# UHF_RFID_READER_IC.net
KiCad netlist of a schematic drawn in Altium Designer
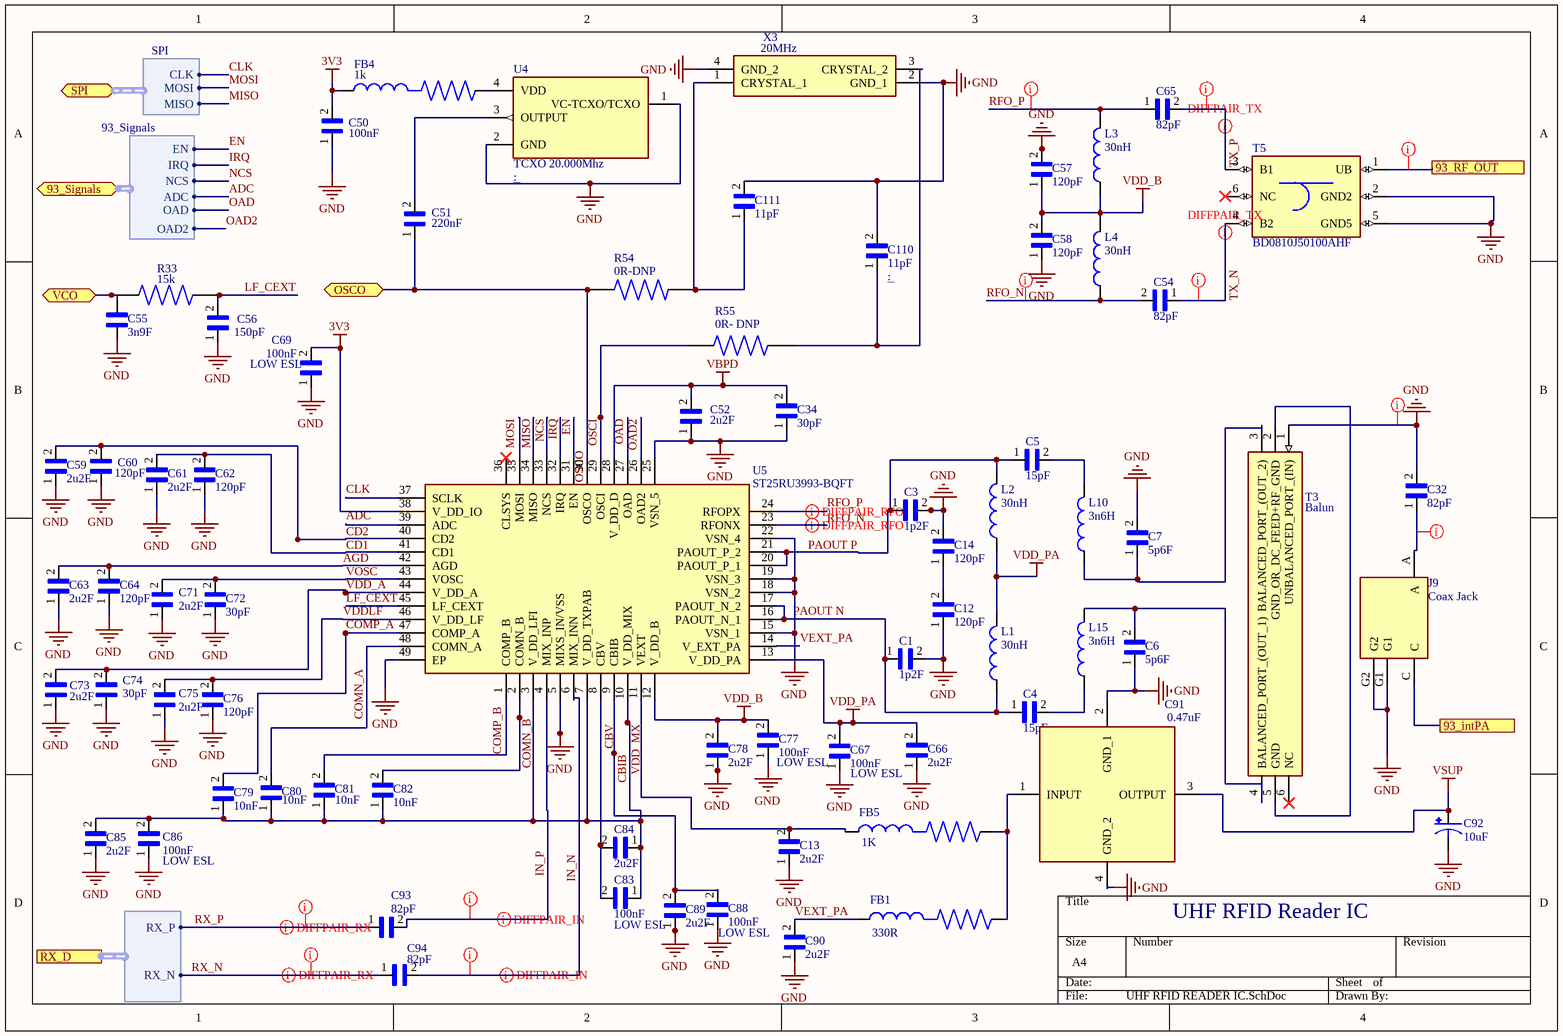
[diagram p0: UHF RFID READER IC.SchDoc]

(export (version "E")
  (design (tool "Eeschema 10.0.6"))
  (components
    (comp (ref "C1")
      (value "1p2F")
      (footprint "CAPC1005X55N")
      (description "SMD Capacitor C0G_EIA_ with Capacitance: 1.2pF Tol. 0.05pF. Rated Voltage: 50Vdc")
      (fields (field (name "MP") "GRM1555C1H1R2WA01D") (field (name "MF") "Murata Electronics"))
      (libsource (lib "GRM1555C1H1R2WA01D") (part "GRM1555C1H1R2WA01D"))
    )
    (comp (ref "C3")
      (value "1p2F")
      (footprint "CAPC1005X55N")
      (description "SMD Capacitor C0G_EIA_ with Capacitance: 1.2pF Tol. 0.05pF. Rated Voltage: 50Vdc")
      (fields (field (name "MP") "GRM1555C1H1R2WA01D") (field (name "MF") "Murata Electronics"))
      (libsource (lib "GRM1555C1H1R2WA01D") (part "GRM1555C1H1R2WA01D"))
    )
    (comp (ref "C4")
      (value "15pF")
      (footprint "CAPC1005X55N")
      (description "0402 15 pF 50 V Â±2% Tolerance C0G SMT Multilayer Ceramic Capacitor")
      (fields (field (name "MP") "GRM1555C1H150GA01D"))
      (libsource (lib "GRM1555C1H150GA01D") (part "GRM1555C1H150GA01D"))
    )
    (comp (ref "C5")
      (value "15pF")
      (footprint "CAPC1005X55N")
      (description "0402 15 pF 50 V Â±2% Tolerance C0G SMT Multilayer Ceramic Capacitor")
      (fields (field (name "MP") "GRM1555C1H150GA01D"))
      (libsource (lib "GRM1555C1H150GA01D") (part "GRM1555C1H150GA01D"))
    )
    (comp (ref "C6")
      (value "5p6F")
      (footprint "CAPC1005X55N")
      (description "SMD Capacitor C0G(EIA) with Capacitance: 5.6pF Tol. 0.25pF. Rated Voltage: 50Vdc")
      (fields (field (name "MF") "Murata") (field (name "MP") "GJM1555C1H5R6CB01D"))
      (libsource (lib "GJM1555C1H5R6CB01D") (part "GJM1555C1H5R6CB01D"))
    )
    (comp (ref "C7")
      (value "5p6F")
      (footprint "CAPC1005X55N")
      (description "SMD Capacitor C0G(EIA) with Capacitance: 5.6pF Tol. 0.25pF. Rated Voltage: 50Vdc")
      (fields (field (name "MF") "Murata") (field (name "MP") "GJM1555C1H5R6CB01D"))
      (libsource (lib "GJM1555C1H5R6CB01D") (part "GJM1555C1H5R6CB01D"))
    )
    (comp (ref "C12")
      (value "120pF")
      (footprint "CAPC0603X33N")
      (description "0201 120 pF 50 V Â±5% Tolerance C0G SMT Multilayer Ceramic Capacitor")
      (fields (field (name "MF") "Murata Electronics") (field (name "MP") "GRM0335C1H121JA01D"))
      (libsource (lib "") (part "GRM0335C1H121JA01D_1"))
    )
    (comp (ref "C13")
      (value "2u2F")
      (footprint "CAPC0603X35N")
      (description "SMD Capacitor X5R(EIA) with Capacitance: 2.2uF Tol. 20%. Rated Voltage: 6.3Vdc")
      (fields (field (name "MP") "GRM033R60J225ME15D"))
      (libsource (lib "GRM033R60J225ME15D") (part "GRM033R60J225ME15D"))
    )
    (comp (ref "C14")
      (value "120pF")
      (footprint "CAPC0603X33N")
      (description "0201 120 pF 50 V Â±5% Tolerance C0G SMT Multilayer Ceramic Capacitor")
      (fields (field (name "MF") "Murata Electronics") (field (name "MP") "GRM0335C1H121JA01D"))
      (libsource (lib "") (part "GRM0335C1H121JA01D_1"))
    )
    (comp (ref "C32")
      (value "82pF")
      (footprint "CAPC1005X55N")
      (description "CAP CER 82PF 50V C0G/NP0 0402")
      (fields (field (name "MP") "GRM1555C1H820GA01J"))
      (libsource (lib "GRM1555C1H820GA01J") (part "GRM1555C1H820GA01J"))
    )
    (comp (ref "C34")
      (value "30pF")
      (footprint "CAPC0603X33N")
      (description "SMD Capacitor C0G(EIA) with Capacitance: 30pF Tol. 2%. Rated Voltage: 50Vdc")
      (fields (field (name "MP") "GRM0335C1H300GA01D"))
      (libsource (lib "GRM0335C1H300GA01D") (part "GRM0335C1H300GA01D"))
    )
    (comp (ref "C50")
      (value "100nF")
      (footprint "CAPC1005X55N")
      (description "SMD Capacitor X7R_EIA_ with Capacitance: 0.10uF Tol. 10%. Rated Voltage: 16Vdc")
      (fields (field (name "MF") "Murata") (field (name "MP") "GRM155R71C104KA88D"))
      (libsource (lib "GRM155R71C104KA88D") (part "GRM155R71C104KA88D"))
    )
    (comp (ref "C51")
      (value "220nF")
      (footprint "CAPC1005X55N")
      (description "CAP CER 0.22UF 35V X5R 0402")
      (fields (field (name "MP") "GRM155R6YA224KE01D"))
      (libsource (lib "GRM155R6YA224KE01D") (part "GRM155R6YA224KE01D"))
    )
    (comp (ref "C52")
      (value "2u2F")
      (footprint "CAPC0603X35N")
      (description "SMD Capacitor X5R(EIA) with Capacitance: 2.2uF Tol. 20%. Rated Voltage: 6.3Vdc")
      (fields (field (name "MP") "GRM033R60J225ME15D"))
      (libsource (lib "GRM033R60J225ME15D") (part "GRM033R60J225ME15D"))
    )
    (comp (ref "C54")
      (value "82pF")
      (footprint "CAPC1005X55N")
      (description "CAP CER 82PF 50V C0G/NP0 0402")
      (fields (field (name "MP") "GRM1555C1H820GA01J"))
      (libsource (lib "") (part "GRM1555C1H820GA01J_3"))
    )
    (comp (ref "C55")
      (value "3n9F")
      (footprint "CAPC1005X55N")
      (description "0402 10 V 3900 pF ±5% Tolerance U2J Monolithic Ceramic Chip Capacitor")
      (fields (field (name "MF") "Murata") (field (name "MP") "GRM1557U1A392JA01D"))
      (libsource (lib "GRM1557U1A392JA01D") (part "GRM1557U1A392JA01D"))
    )
    (comp (ref "C56")
      (value "150pF")
      (footprint "CAPC1005X55N")
      (description "Cap Ceramic 150pF 50V C0G 1% SMD 0402 125Â°C Paper T/R")
      (fields (field (name "MP") "GRM1555C1H151FA01D"))
      (libsource (lib "GRM1555C1H151FA01D") (part "GRM1555C1H151FA01D"))
    )
    (comp (ref "C57")
      (value "120pF")
      (footprint "CAPC0603X33N")
      (description "0201 120 pF 50 V Â±5% Tolerance C0G SMT Multilayer Ceramic Capacitor")
      (fields (field (name "MF") "Murata Electronics") (field (name "MP") "GRM0335C1H121JA01D"))
      (libsource (lib "") (part "GRM0335C1H121JA01D_2"))
    )
    (comp (ref "C58")
      (value "120pF")
      (footprint "CAPC0603X33N")
      (description "0201 120 pF 50 V Â±5% Tolerance C0G SMT Multilayer Ceramic Capacitor")
      (fields (field (name "MF") "Murata Electronics") (field (name "MP") "GRM0335C1H121JA01D"))
      (libsource (lib "") (part "GRM0335C1H121JA01D_2"))
    )
    (comp (ref "C59")
      (value "2u2F")
      (footprint "CAPC0603X35N")
      (description "SMD Capacitor X5R(EIA) with Capacitance: 2.2uF Tol. 20%. Rated Voltage: 6.3Vdc")
      (fields (field (name "MP") "GRM033R60J225ME15D"))
      (libsource (lib "GRM033R60J225ME15D") (part "GRM033R60J225ME15D"))
    )
    (comp (ref "C60")
      (value "120pF")
      (footprint "CAPC0603X33N")
      (description "0201 120 pF 50 V Â±5% Tolerance C0G SMT Multilayer Ceramic Capacitor")
      (fields (field (name "MF") "Murata Electronics") (field (name "MP") "GRM0335C1H121JA01D"))
      (libsource (lib "GRM0335C1H121JA01D") (part "GRM0335C1H121JA01D"))
    )
    (comp (ref "C61")
      (value "2u2F")
      (footprint "CAPC0603X35N")
      (description "SMD Capacitor X5R(EIA) with Capacitance: 2.2uF Tol. 20%. Rated Voltage: 6.3Vdc")
      (fields (field (name "MP") "GRM033R60J225ME15D"))
      (libsource (lib "GRM033R60J225ME15D") (part "GRM033R60J225ME15D"))
    )
    (comp (ref "C62")
      (value "120pF")
      (footprint "CAPC0603X33N")
      (description "0201 120 pF 50 V Â±5% Tolerance C0G SMT Multilayer Ceramic Capacitor")
      (fields (field (name "MF") "Murata Electronics") (field (name "MP") "GRM0335C1H121JA01D"))
      (libsource (lib "GRM0335C1H121JA01D") (part "GRM0335C1H121JA01D"))
    )
    (comp (ref "C63")
      (value "2u2F")
      (footprint "CAPC0603X35N")
      (description "SMD Capacitor X5R(EIA) with Capacitance: 2.2uF Tol. 20%. Rated Voltage: 6.3Vdc")
      (fields (field (name "MP") "GRM033R60J225ME15D"))
      (libsource (lib "GRM033R60J225ME15D") (part "GRM033R60J225ME15D"))
    )
    (comp (ref "C64")
      (value "120pF")
      (footprint "CAPC0603X33N")
      (description "0201 120 pF 50 V Â±5% Tolerance C0G SMT Multilayer Ceramic Capacitor")
      (fields (field (name "MF") "Murata Electronics") (field (name "MP") "GRM0335C1H121JA01D"))
      (libsource (lib "GRM0335C1H121JA01D") (part "GRM0335C1H121JA01D"))
    )
    (comp (ref "C65")
      (value "82pF")
      (footprint "CAPC1005X55N")
      (description "CAP CER 82PF 50V C0G/NP0 0402")
      (fields (field (name "MP") "GRM1555C1H820GA01J"))
      (libsource (lib "") (part "GRM1555C1H820GA01J_2"))
    )
    (comp (ref "C66")
      (value "2u2F")
      (footprint "CAPC0603X35N")
      (description "SMD Capacitor X5R(EIA) with Capacitance: 2.2uF Tol. 20%. Rated Voltage: 6.3Vdc")
      (fields (field (name "MP") "GRM033R60J225ME15D"))
      (libsource (lib "GRM033R60J225ME15D") (part "GRM033R60J225ME15D"))
    )
    (comp (ref "C67")
      (value "100nF")
      (footprint "CAPC0510X35N")
      (description "SMD Capacitor X6S(EIA) with Capacitance: 0.10uF Tol. 20%. Rated Voltage: 6.3Vdc")
      (fields (field (name "MF") "Murata") (field (name "MP") "LLL153C80J104ME01E"))
      (libsource (lib "LLL153C80J104ME01E") (part "LLL153C80J104ME01E"))
    )
    (comp (ref "C69")
      (value "100nF")
      (footprint "CAPC0510X35N")
      (description "SMD Capacitor X6S(EIA) with Capacitance: 0.10uF Tol. 20%. Rated Voltage: 6.3Vdc")
      (fields (field (name "MF") "Murata") (field (name "MP") "LLL153C80J104ME01E"))
      (libsource (lib "LLL153C80J104ME01E") (part "LLL153C80J104ME01E"))
    )
    (comp (ref "C71")
      (value "2u2F")
      (footprint "CAPC0603X35N")
      (description "SMD Capacitor X5R(EIA) with Capacitance: 2.2uF Tol. 20%. Rated Voltage: 6.3Vdc")
      (fields (field (name "MP") "GRM033R60J225ME15D"))
      (libsource (lib "GRM033R60J225ME15D") (part "GRM033R60J225ME15D"))
    )
    (comp (ref "C72")
      (value "30pF")
      (footprint "CAPC0603X33N")
      (description "SMD Capacitor C0G(EIA) with Capacitance: 30pF Tol. 2%. Rated Voltage: 50Vdc")
      (fields (field (name "MP") "GRM0335C1H300GA01D"))
      (libsource (lib "GRM0335C1H300GA01D") (part "GRM0335C1H300GA01D"))
    )
    (comp (ref "C73")
      (value "2u2F")
      (footprint "CAPC0603X35N")
      (description "SMD Capacitor X5R(EIA) with Capacitance: 2.2uF Tol. 20%. Rated Voltage: 6.3Vdc")
      (fields (field (name "MP") "GRM033R60J225ME15D"))
      (libsource (lib "GRM033R60J225ME15D") (part "GRM033R60J225ME15D"))
    )
    (comp (ref "C74")
      (value "30pF")
      (footprint "CAPC0603X33N")
      (description "SMD Capacitor C0G(EIA) with Capacitance: 30pF Tol. 2%. Rated Voltage: 50Vdc")
      (fields (field (name "MP") "GRM0335C1H300GA01D"))
      (libsource (lib "GRM0335C1H300GA01D") (part "GRM0335C1H300GA01D"))
    )
    (comp (ref "C75")
      (value "2u2F")
      (footprint "CAPC0603X35N")
      (description "SMD Capacitor X5R(EIA) with Capacitance: 2.2uF Tol. 20%. Rated Voltage: 6.3Vdc")
      (fields (field (name "MP") "GRM033R60J225ME15D"))
      (libsource (lib "GRM033R60J225ME15D") (part "GRM033R60J225ME15D"))
    )
    (comp (ref "C76")
      (value "120pF")
      (footprint "CAPC0603X33N")
      (description "0201 120 pF 50 V Â±5% Tolerance C0G SMT Multilayer Ceramic Capacitor")
      (fields (field (name "MF") "Murata Electronics") (field (name "MP") "GRM0335C1H121JA01D"))
      (libsource (lib "GRM0335C1H121JA01D") (part "GRM0335C1H121JA01D"))
    )
    (comp (ref "C77")
      (value "100nF")
      (footprint "CAPC0510X35N")
      (description "SMD Capacitor X6S(EIA) with Capacitance: 0.10uF Tol. 20%. Rated Voltage: 6.3Vdc")
      (fields (field (name "MF") "Murata") (field (name "MP") "LLL153C80J104ME01E"))
      (libsource (lib "LLL153C80J104ME01E") (part "LLL153C80J104ME01E"))
    )
    (comp (ref "C78")
      (value "2u2F")
      (footprint "CAPC0603X35N")
      (description "SMD Capacitor X5R(EIA) with Capacitance: 2.2uF Tol. 20%. Rated Voltage: 6.3Vdc")
      (fields (field (name "MP") "GRM033R60J225ME15D"))
      (libsource (lib "GRM033R60J225ME15D") (part "GRM033R60J225ME15D"))
    )
    (comp (ref "C79")
      (value "10nF")
      (footprint "CAPC0603X33N")
      (description "SMD Capacitor X7R(EIA) with Capacitance: 10000pF Tol. 10%. Rated Voltage: 10Vdc")
      (fields (field (name "MP") "GRM033R71A103KA01D") (field (name "MF") "Murata"))
      (libsource (lib "GRM033R71A103KA01D") (part "GRM033R71A103KA01D"))
    )
    (comp (ref "C80")
      (value "10nF")
      (footprint "CAPC0603X33N")
      (description "SMD Capacitor X7R(EIA) with Capacitance: 10000pF Tol. 10%. Rated Voltage: 10Vdc")
      (fields (field (name "MP") "GRM033R71A103KA01D") (field (name "MF") "Murata"))
      (libsource (lib "GRM033R71A103KA01D") (part "GRM033R71A103KA01D"))
    )
    (comp (ref "C81")
      (value "10nF")
      (footprint "CAPC0603X33N")
      (description "SMD Capacitor X7R(EIA) with Capacitance: 10000pF Tol. 10%. Rated Voltage: 10Vdc")
      (fields (field (name "MP") "GRM033R71A103KA01D") (field (name "MF") "Murata"))
      (libsource (lib "GRM033R71A103KA01D") (part "GRM033R71A103KA01D"))
    )
    (comp (ref "C82")
      (value "10nF")
      (footprint "CAPC0603X33N")
      (description "SMD Capacitor X7R(EIA) with Capacitance: 10000pF Tol. 10%. Rated Voltage: 10Vdc")
      (fields (field (name "MP") "GRM033R71A103KA01D") (field (name "MF") "Murata"))
      (libsource (lib "GRM033R71A103KA01D") (part "GRM033R71A103KA01D"))
    )
    (comp (ref "C83")
      (value "100nF")
      (footprint "CAPC0510X35N")
      (description "SMD Capacitor X6S(EIA) with Capacitance: 0.10uF Tol. 20%. Rated Voltage: 6.3Vdc")
      (fields (field (name "MF") "Murata") (field (name "MP") "LLL153C80J104ME01E"))
      (libsource (lib "") (part "LLL153C80J104ME01E_1"))
    )
    (comp (ref "C84")
      (value "2u2F")
      (footprint "CAPC0603X35N")
      (description "SMD Capacitor X5R(EIA) with Capacitance: 2.2uF Tol. 20%. Rated Voltage: 6.3Vdc")
      (fields (field (name "MP") "GRM033R60J225ME15D"))
      (libsource (lib "") (part "GRM033R60J225ME15D_1"))
    )
    (comp (ref "C85")
      (value "2u2F")
      (footprint "CAPC0603X35N")
      (description "SMD Capacitor X5R(EIA) with Capacitance: 2.2uF Tol. 20%. Rated Voltage: 6.3Vdc")
      (fields (field (name "MP") "GRM033R60J225ME15D"))
      (libsource (lib "GRM033R60J225ME15D") (part "GRM033R60J225ME15D"))
    )
    (comp (ref "C86")
      (value "100nF")
      (footprint "CAPC0510X35N")
      (description "SMD Capacitor X6S(EIA) with Capacitance: 0.10uF Tol. 20%. Rated Voltage: 6.3Vdc")
      (fields (field (name "MF") "Murata") (field (name "MP") "LLL153C80J104ME01E"))
      (libsource (lib "LLL153C80J104ME01E") (part "LLL153C80J104ME01E"))
    )
    (comp (ref "C88")
      (value "100nF")
      (footprint "CAPC0510X35N")
      (description "SMD Capacitor X6S(EIA) with Capacitance: 0.10uF Tol. 20%. Rated Voltage: 6.3Vdc")
      (fields (field (name "MF") "Murata") (field (name "MP") "LLL153C80J104ME01E"))
      (libsource (lib "LLL153C80J104ME01E") (part "LLL153C80J104ME01E"))
    )
    (comp (ref "C89")
      (value "2u2F")
      (footprint "CAPC0603X35N")
      (description "SMD Capacitor X5R(EIA) with Capacitance: 2.2uF Tol. 20%. Rated Voltage: 6.3Vdc")
      (fields (field (name "MP") "GRM033R60J225ME15D"))
      (libsource (lib "GRM033R60J225ME15D") (part "GRM033R60J225ME15D"))
    )
    (comp (ref "C90")
      (value "2u2F")
      (footprint "CAPC0603X35N")
      (description "SMD Capacitor X5R(EIA) with Capacitance: 2.2uF Tol. 20%. Rated Voltage: 6.3Vdc")
      (fields (field (name "MP") "GRM033R60J225ME15D"))
      (libsource (lib "GRM033R60J225ME15D") (part "GRM033R60J225ME15D"))
    )
    (comp (ref "C91")
      (value "0.47uF")
      (footprint "SamacSys:NFM18CC101R1C3D")
      (description "Capacitor")
      (fields
        (field (name "MANUFACTURER_PART_NUMBER") "NFM18PS474R0J3D")
        (field (name "MOUSER PART NUMBER") "81-NFM18PS474R0J3D")
      )
      (libsource (lib "*") (part "NFM18PS474R0J3D"))
    )
    (comp (ref "C92")
      (value "10uF")
      (footprint "2917(POL)")
      (description "10 ÂµF 16 V Aluminum - Polymer Capacitors 2917 (7343 Metric) 60mOhm 1000 Hrs @ 105Â°C")
      (fields (field (name "MF") "Murata Electronics") (field (name "MP") "ECASD41C106M060K00"))
      (libsource (lib "ECASD41C106M060K00") (part "ECASD41C106M060K00"))
    )
    (comp (ref "C93")
      (value "82pF")
      (footprint "CAPC1005X55N")
      (description "CAP CER 82PF 50V C0G/NP0 0402")
      (fields (field (name "MP") "GRM1555C1H820GA01J"))
      (libsource (lib "") (part "GRM1555C1H820GA01J_1"))
    )
    (comp (ref "C94")
      (value "82pF")
      (footprint "CAPC1005X55N")
      (description "CAP CER 82PF 50V C0G/NP0 0402")
      (fields (field (name "MP") "GRM1555C1H820GA01J"))
      (libsource (lib "") (part "GRM1555C1H820GA01J_1"))
    )
    (comp (ref "C110")
      (value "11pF")
      (footprint "CAPC1005X55N")
      (description "SMD Capacitor C0G(EIA) with Capacitance: 11pF Tol. 2%. Rated Voltage: 50Vdc")
      (fields (field (name "MP") "GJM1555C1H110GB01D") (field (name "DIGI-KEY_PART_NUMBER") "490-6072-1-ND"))
      (libsource (lib "GJM1555C1H110GB01D") (part "GJM1555C1H110GB01D"))
    )
    (comp (ref "C111")
      (value "11pF")
      (footprint "CAPC1005X55N")
      (description "SMD Capacitor C0G(EIA) with Capacitance: 11pF Tol. 2%. Rated Voltage: 50Vdc")
      (fields (field (name "MP") "GJM1555C1H110GB01D") (field (name "DIGI-KEY_PART_NUMBER") "490-6072-1-ND"))
      (libsource (lib "GJM1555C1H110GB01D") (part "GJM1555C1H110GB01D"))
    )
    (comp (ref "FB1")
      (value "330R")
      (footprint "BEADC1005X55N")
      (description "330 Ohms @ 100MHz 1 Power Line Ferrite Bead 0402 (1005 Metric) 1.2A 150mOhm")
      (fields (field (name "MP") "BLM15PX331SN1D") (field (name "MF") "Murata Electronics"))
      (libsource (lib "BLM15PX331SN1D") (part "BLM15PX331SN1D"))
    )
    (comp (ref "FB4")
      (value "1k")
      (footprint "BEADC1005X55N")
      (description "1 kOhms @ 100MHz 1 Signal Line Ferrite Bead 0402 _1005 Metric_ 250mA 1.1Ohm")
      (fields (field (name "MF") "Murata") (field (name "DIGI-KEY_PART_NUMBER") "490-3999-1-ND"))
      (libsource (lib "BLM15HG102SN1D") (part "BLM15HG102SN1D"))
    )
    (comp (ref "FB5")
      (value "1K")
      (footprint "BEADC1005X55N")
      (description "1 kOhms @ 100MHz 1 Signal Line Ferrite Bead 0402 _1005 Metric_ 250mA 1.1Ohm")
      (fields (field (name "MF") "Murata") (field (name "DIGI-KEY_PART_NUMBER") "490-3999-1-ND"))
      (libsource (lib "BLM15HG102SN1D") (part "BLM15HG102SN1D"))
    )
    (comp (ref "J9")
      (value "Coax Jack")
      (footprint "SW_MS-156HF(01)")
      (description "Coaxial Switch - 4mm Plug Dia Connector Receptacle, Female Socket 50Ohm Surface Mount Solder")
      (fields (field (name "MP") "MS-156HF(01)") (field (name "MF") "Hirose Electric"))
      (libsource (lib "MS-156HF_01_") (part "MS-156HF(01)"))
    )
    (comp (ref "L1")
      (value "30nH")
      (footprint "INDC1005X60N")
      (description "Inductor with Inductance: 30nH Tol. +/-2%, Package: 0402 (1005)")
      (fields (field (name "MP") "LQW15AN30NG00D") (field (name "MF") "Murata"))
      (libsource (lib "LQW15AN30NG00D") (part "LQW15AN30NG00D"))
    )
    (comp (ref "L2")
      (value "30nH")
      (footprint "INDC1005X60N")
      (description "Inductor with Inductance: 30nH Tol. +/-2%, Package: 0402 (1005)")
      (fields (field (name "MP") "LQW15AN30NG00D") (field (name "MF") "Murata"))
      (libsource (lib "LQW15AN30NG00D") (part "LQW15AN30NG00D"))
    )
    (comp (ref "L3")
      (value "30nH")
      (footprint "INDC1005X60N")
      (description "Inductor with Inductance: 30nH Tol. +/-2%, Package: 0402 (1005)")
      (fields (field (name "MP") "LQW15AN30NG00D") (field (name "MF") "Murata"))
      (libsource (lib "LQW15AN30NG00D") (part "LQW15AN30NG00D"))
    )
    (comp (ref "L4")
      (value "30nH")
      (footprint "INDC1005X60N")
      (description "Inductor with Inductance: 30nH Tol. +/-2%, Package: 0402 (1005)")
      (fields (field (name "MP") "LQW15AN30NG00D") (field (name "MF") "Murata"))
      (libsource (lib "LQW15AN30NG00D") (part "LQW15AN30NG00D"))
    )
    (comp (ref "L10")
      (value "3n6H")
      (footprint "INDC1006X60N")
      (description "FIXED IND 3.6NH 900MA 40 MOHM")
      (fields (field (name "MP") "LQW15AN3N6C10D"))
      (libsource (lib "LQW15AN3N6C10D") (part "LQW15AN3N6C10D"))
    )
    (comp (ref "L15")
      (value "3n6H")
      (footprint "INDC1006X60N")
      (description "FIXED IND 3.6NH 900MA 40 MOHM")
      (fields (field (name "MP") "LQW15AN3N6C10D"))
      (libsource (lib "LQW15AN3N6C10D") (part "LQW15AN3N6C10D"))
    )
    (comp (ref "R33")
      (value "15k")
      (footprint "RES_ERJ-2GEJ153X")
      (description "15 kOhms ±5% 0.1W, 1/10W Chip Resistor 0402 (1005 Metric) Automotive AEC-Q200 Thick Film")
      (fields (field (name "MF") "Panasonic Electronic") (field (name "MP") "ERJ-2GEJ153X"))
      (libsource (lib "ERJ-2GEJ153X") (part "ERJ-2GEJ153X"))
    )
    (comp (ref "R54")
      (value "0R-DNP")
      (footprint "RESC1607X60N")
      (description "Thick film general purpose")
      (fields (field (name "MP") "RC0603JR-070RL"))
      (libsource (lib "RC0603JR-070RL") (part "RC0603JR-070RL"))
    )
    (comp (ref "R55")
      (value "0R- DNP")
      (footprint "RESC1607X60N")
      (description "Thick film general purpose")
      (fields (field (name "MP") "RC0603JR-070RL"))
      (libsource (lib "RC0603JR-070RL") (part "RC0603JR-070RL"))
    )
    (comp (ref "T3")
      (value "Balun")
      (footprint "SamacSys:0900BL15C050E")
      (description "Filter")
      (fields
        (field (name "MANUFACTURER_PART_NUMBER") "0900BL15C050E")
        (field (name "MOUSER PART NUMBER") "609-0900BL15C050E")
      )
      (libsource (lib "*") (part "0900BL15C050E"))
    )
    (comp (ref "T5")
      (value "BD0810J50100AHF")
      (footprint "BD0810J50100AHF")
      (description "Signal Conditioning 800-1000MHz 50/100 Ohm IL=.95dB")
      (fields (field (name "MF") "ttm technologies"))
      (libsource (lib "BD0810J50100AHF") (part "BD0810J50100AHF"))
    )
    (comp (ref "U4")
      (value "TCXO 20.000Mhz")
      (footprint "OSCCC320X250X100N")
      (description "20MHz TCXO Clipped Sine Wave Oscillator 2.8V ~ 3.3V 4-SMD, No Lead")
      (fields (field (name "MP") "TXETDCSANF-20.000000") (field (name "MF") "Taitien"))
      (libsource (lib "TXETDCSANF-20.000000") (part "TXETDCSANF-20.000000"))
    )
    (comp (ref "U5")
      (value "ST25RU3993-BQFT")
      (footprint "reader ic:FP-ST25RU3993-BQFT-IPC_A")
      (description "Integrated Circuit")
      (fields (field (name "MOUSER PART NUMBER") "511-ST25RU3993-BQFT"))
      (libsource (lib "SamacSys") (part "ST25RU3993-BQFT"))
    )
    (comp (ref "X3")
      (value "20MHz")
      (footprint "SamacSys:NX3225SA20000000MHZB2")
      (description "Crystal or Oscillator")
      (fields
        (field (name "MANUFACTURER_PART_NUMBER") "NX3225SA-20.000000MHZ-B2")
        (field (name "MOUSER PART NUMBER") "344-NX3225SA20MHZB2")
      )
      (libsource (lib "*") (part "NX3225SA-20.000000MHZ-B2"))
    )
  )
  (nets
    (net (code "4") (name "/93_RF_OUT") (class "Default")
      (node (ref "T5") (pin "1") (pinfunction "UB_1") (pintype "bidirectional"))
    )
    (net (code "5") (name "/93_intPA") (class "Default")
      (node (ref "J9") (pin "C") (pinfunction "C_C") (pintype "passive"))
    )
    (net (code "6") (name "/ADC") (class "Default")
      (node (ref "U5") (pin "39") (pinfunction "ADC_39") (pintype "passive"))
    )
    (net (code "7") (name "/AGD") (class "Default")
      (node (ref "C63") (pin "2") (pinfunction "2_2") (pintype "passive"))
      (node (ref "C64") (pin "2") (pinfunction "2_2") (pintype "passive"))
      (node (ref "U5") (pin "42") (pinfunction "AGD_42") (pintype "passive"))
    )
    (net (code "8") (name "/CBIB") (class "Default")
      (node (ref "C88") (pin "2") (pinfunction "2_2") (pintype "passive"))
      (node (ref "C89") (pin "2") (pinfunction "2_2") (pintype "passive"))
      (node (ref "U5") (pin "9") (pinfunction "CBIB_9") (pintype "passive"))
    )
    (net (code "9") (name "/CBV") (class "Default")
      (node (ref "C83") (pin "2") (pinfunction "2_2") (pintype "passive"))
      (node (ref "C84") (pin "2") (pinfunction "2_2") (pintype "passive"))
      (node (ref "U5") (pin "8") (pinfunction "CBV_8") (pintype "passive"))
    )
    (net (code "10") (name "/CD1") (class "Default")
      (node (ref "C61") (pin "2") (pinfunction "2_2") (pintype "passive"))
      (node (ref "C62") (pin "2") (pinfunction "2_2") (pintype "passive"))
      (node (ref "U5") (pin "41") (pinfunction "CD1_41") (pintype "passive"))
    )
    (net (code "11") (name "/CD2") (class "Default")
      (node (ref "C59") (pin "2") (pinfunction "2_2") (pintype "passive"))
      (node (ref "C60") (pin "2") (pinfunction "2_2") (pintype "passive"))
      (node (ref "U5") (pin "40") (pinfunction "CD2_40") (pintype "passive"))
    )
    (net (code "12") (name "/CLK") (class "Default")
      (node (ref "U5") (pin "37") (pinfunction "SCLK_37") (pintype "passive"))
    )
    (net (code "13") (name "/COMN_A") (class "Default")
      (node (ref "C80") (pin "2") (pinfunction "2_2") (pintype "passive"))
      (node (ref "U5") (pin "48") (pinfunction "COMN_A_48") (pintype "passive"))
    )
    (net (code "14") (name "/COMN_B") (class "Default")
      (node (ref "C82") (pin "2") (pinfunction "2_2") (pintype "passive"))
      (node (ref "U5") (pin "2") (pinfunction "COMN_B_2") (pintype "passive"))
    )
    (net (code "15") (name "/COMP_A") (class "Default")
      (node (ref "C79") (pin "2") (pinfunction "2_2") (pintype "passive"))
      (node (ref "U5") (pin "47") (pinfunction "COMP_A_47") (pintype "passive"))
    )
    (net (code "16") (name "/COMP_B") (class "Default")
      (node (ref "C81") (pin "2") (pinfunction "2_2") (pintype "passive"))
      (node (ref "U5") (pin "1") (pinfunction "COMP_B_1") (pintype "passive"))
    )
    (net (code "17") (name "/EN") (class "Default")
      (node (ref "U5") (pin "31") (pinfunction "EN_31") (pintype "passive"))
    )
    (net (code "18") (name "/IN_N") (class "Default")
      (node (ref "C94") (pin "2") (pinfunction "2_2") (pintype "passive"))
      (node (ref "U5") (pin "6") (pinfunction "MIX_INN_6") (pintype "passive"))
    )
    (net (code "19") (name "/IN_P") (class "Default")
      (node (ref "C93") (pin "2") (pinfunction "2_2") (pintype "passive"))
      (node (ref "U5") (pin "4") (pinfunction "MIX_INP_4") (pintype "passive"))
    )
    (net (code "20") (name "/IRQ") (class "Default")
      (node (ref "U5") (pin "32") (pinfunction "IRQ_32") (pintype "passive"))
    )
    (net (code "21") (name "/LF_CEXT") (class "Default")
      (node (ref "C56") (pin "2") (pinfunction "2_2") (pintype "passive"))
      (node (ref "R33") (pin "2") (pinfunction "2_2") (pintype "passive"))
      (node (ref "U5") (pin "45") (pinfunction "LF_CEXT_45") (pintype "passive"))
    )
    (net (code "22") (name "/MISO") (class "Default")
      (node (ref "U5") (pin "34") (pinfunction "MISO_34") (pintype "passive"))
    )
    (net (code "23") (name "/MOSI") (class "Default")
      (node (ref "U5") (pin "35") (pinfunction "MOSI_35") (pintype "passive"))
    )
    (net (code "24") (name "/NCS") (class "Default")
      (node (ref "U5") (pin "33") (pinfunction "NCS_33") (pintype "passive"))
    )
    (net (code "25") (name "/OAD") (class "Default")
      (node (ref "U5") (pin "27") (pinfunction "OAD_27") (pintype "passive"))
    )
    (net (code "26") (name "/OAD2") (class "Default")
      (node (ref "U5") (pin "26") (pinfunction "OAD2_26") (pintype "passive"))
    )
    (net (code "27") (name "/OSCI") (class "Default")
      (node (ref "R55") (pin "1") (pinfunction "1_1") (pintype "passive"))
      (node (ref "U5") (pin "29") (pinfunction "OSCI_29") (pintype "passive"))
    )
    (net (code "28") (name "/OSCO") (class "Default")
      (node (ref "C51") (pin "1") (pinfunction "1_1") (pintype "passive"))
      (node (ref "R54") (pin "1") (pinfunction "1_1") (pintype "passive"))
      (node (ref "U5") (pin "30") (pinfunction "OSCO_30") (pintype "passive"))
    )
    (net (code "29") (name "/PAOUT N") (class "Default")
      (node (ref "C1") (pin "1") (pinfunction "1_1") (pintype "passive"))
      (node (ref "C4") (pin "1") (pinfunction "1_1") (pintype "passive"))
      (node (ref "L1") (pin "1") (pinfunction "1_1") (pintype "passive"))
      (node (ref "U5") (pin "16") (pinfunction "PAOUT_N_1_16") (pintype "passive"))
      (node (ref "U5") (pin "17") (pinfunction "PAOUT_N_2_17") (pintype "passive"))
    )
    (net (code "30") (name "/PAOUT P") (class "Default")
      (node (ref "C3") (pin "1") (pinfunction "1_1") (pintype "passive"))
      (node (ref "C5") (pin "1") (pinfunction "1_1") (pintype "passive"))
      (node (ref "L2") (pin "2") (pinfunction "2_2") (pintype "passive"))
      (node (ref "U5") (pin "20") (pinfunction "PAOUT_P_1_20") (pintype "passive"))
      (node (ref "U5") (pin "21") (pinfunction "PAOUT_P_2_21") (pintype "passive"))
    )
    (net (code "31") (name "/RFO_N") (class "Default")
      (node (ref "C54") (pin "2") (pinfunction "2_2") (pintype "passive"))
      (node (ref "L4") (pin "1") (pinfunction "1_1") (pintype "passive"))
      (node (ref "U5") (pin "23") (pinfunction "RFONX_23") (pintype "passive"))
    )
    (net (code "32") (name "/RFO_P") (class "Default")
      (node (ref "C65") (pin "1") (pinfunction "1_1") (pintype "passive"))
      (node (ref "L3") (pin "2") (pinfunction "2_2") (pintype "passive"))
      (node (ref "U5") (pin "24") (pinfunction "RFOPX_24") (pintype "passive"))
    )
    (net (code "33") (name "/RX_N") (class "Default")
      (node (ref "C94") (pin "1") (pinfunction "1_1") (pintype "passive"))
    )
    (net (code "34") (name "/RX_P") (class "Default")
      (node (ref "C93") (pin "1") (pinfunction "1_1") (pintype "passive"))
    )
    (net (code "35") (name "/TX_N") (class "Default")
      (node (ref "C54") (pin "1") (pinfunction "1_1") (pintype "passive"))
      (node (ref "T5") (pin "4") (pinfunction "B2_4") (pintype "bidirectional"))
    )
    (net (code "36") (name "/TX_P") (class "Default")
      (node (ref "C65") (pin "2") (pinfunction "2_2") (pintype "passive"))
      (node (ref "T5") (pin "3") (pinfunction "B1_3") (pintype "bidirectional"))
    )
    (net (code "37") (name "/VCO") (class "Default")
      (node (ref "C55") (pin "2") (pinfunction "2_2") (pintype "passive"))
      (node (ref "R33") (pin "1") (pinfunction "1_1") (pintype "passive"))
    )
    (net (code "38") (name "/VDDLF") (class "Default")
      (node (ref "C75") (pin "2") (pinfunction "2_2") (pintype "passive"))
      (node (ref "C76") (pin "2") (pinfunction "2_2") (pintype "passive"))
      (node (ref "U5") (pin "46") (pinfunction "V_DD_LF_46") (pintype "passive"))
    )
    (net (code "39") (name "/VDD_A") (class "Default")
      (node (ref "C73") (pin "2") (pinfunction "2_2") (pintype "passive"))
      (node (ref "C74") (pin "2") (pinfunction "2_2") (pintype "passive"))
      (node (ref "U5") (pin "44") (pinfunction "V_DD_A_44") (pintype "passive"))
    )
    (net (code "40") (name "/VDD_MX") (class "Default")
      (node (ref "C79") (pin "1") (pinfunction "1_1") (pintype "passive"))
      (node (ref "C80") (pin "1") (pinfunction "1_1") (pintype "passive"))
      (node (ref "C81") (pin "1") (pinfunction "1_1") (pintype "passive"))
      (node (ref "C82") (pin "1") (pinfunction "1_1") (pintype "passive"))
      (node (ref "C83") (pin "1") (pinfunction "1_1") (pintype "passive"))
      (node (ref "C84") (pin "1") (pinfunction "1_1") (pintype "passive"))
      (node (ref "C85") (pin "2") (pinfunction "2_2") (pintype "passive"))
      (node (ref "C86") (pin "2") (pinfunction "2_2") (pintype "passive"))
      (node (ref "U5") (pin "10") (pinfunction "V_DD_MIX_10") (pintype "passive"))
      (node (ref "U5") (pin "3") (pinfunction "V_DD_LFI_3") (pintype "passive"))
      (node (ref "U5") (pin "7") (pinfunction "V_DD_TXPAB_7") (pintype "passive"))
    )
    (net (code "41") (name "/VEXT_PA") (class "Default")
      (node (ref "C90") (pin "2") (pinfunction "2_2") (pintype "passive"))
      (node (ref "FB1") (pin "1") (pinfunction "1_1") (pintype "passive"))
      (node (ref "U5") (pin "14") (pinfunction "V_EXT_PA_14") (pintype "passive"))
    )
    (net (code "42") (name "/VOSC") (class "Default")
      (node (ref "C71") (pin "2") (pinfunction "2_2") (pintype "passive"))
      (node (ref "C72") (pin "2") (pinfunction "2_2") (pintype "passive"))
      (node (ref "U5") (pin "43") (pinfunction "VOSC_43") (pintype "passive"))
    )
    (net (code "46") (name "3V3") (class "Default")
      (node (ref "C50") (pin "2") (pinfunction "2_2") (pintype "passive"))
      (node (ref "C69") (pin "2") (pinfunction "2_2") (pintype "passive"))
      (node (ref "FB4") (pin "1") (pinfunction "1_1") (pintype "passive"))
      (node (ref "U5") (pin "38") (pinfunction "V_DD_IO_38") (pintype "passive"))
    )
    (net (code "47") (name "GND") (class "Default")
      (node (ref "C1") (pin "2") (pinfunction "2_2") (pintype "passive"))
      (node (ref "C110") (pin "2") (pinfunction "2_2") (pintype "passive"))
      (node (ref "C111") (pin "2") (pinfunction "2_2") (pintype "passive"))
      (node (ref "C12") (pin "1") (pinfunction "1_1") (pintype "passive"))
      (node (ref "C13") (pin "1") (pinfunction "1_1") (pintype "passive"))
      (node (ref "C14") (pin "2") (pinfunction "2_2") (pintype "passive"))
      (node (ref "C3") (pin "2") (pinfunction "2_2") (pintype "passive"))
      (node (ref "C32") (pin "2") (pinfunction "2_2") (pintype "passive"))
      (node (ref "C34") (pin "1") (pinfunction "1_1") (pintype "passive"))
      (node (ref "C50") (pin "1") (pinfunction "1_1") (pintype "passive"))
      (node (ref "C52") (pin "1") (pinfunction "1_1") (pintype "passive"))
      (node (ref "C55") (pin "1") (pinfunction "1_1") (pintype "passive"))
      (node (ref "C56") (pin "1") (pinfunction "1_1") (pintype "passive"))
      (node (ref "C57") (pin "2") (pinfunction "2_2") (pintype "passive"))
      (node (ref "C58") (pin "1") (pinfunction "1_1") (pintype "passive"))
      (node (ref "C59") (pin "1") (pinfunction "1_1") (pintype "passive"))
      (node (ref "C6") (pin "1") (pinfunction "1_1") (pintype "passive"))
      (node (ref "C60") (pin "1") (pinfunction "1_1") (pintype "passive"))
      (node (ref "C61") (pin "1") (pinfunction "1_1") (pintype "passive"))
      (node (ref "C62") (pin "1") (pinfunction "1_1") (pintype "passive"))
      (node (ref "C63") (pin "1") (pinfunction "1_1") (pintype "passive"))
      (node (ref "C64") (pin "1") (pinfunction "1_1") (pintype "passive"))
      (node (ref "C66") (pin "1") (pinfunction "1_1") (pintype "passive"))
      (node (ref "C67") (pin "1") (pinfunction "1_1") (pintype "passive"))
      (node (ref "C69") (pin "1") (pinfunction "1_1") (pintype "passive"))
      (node (ref "C7") (pin "2") (pinfunction "2_2") (pintype "passive"))
      (node (ref "C71") (pin "1") (pinfunction "1_1") (pintype "passive"))
      (node (ref "C72") (pin "1") (pinfunction "1_1") (pintype "passive"))
      (node (ref "C73") (pin "1") (pinfunction "1_1") (pintype "passive"))
      (node (ref "C74") (pin "1") (pinfunction "1_1") (pintype "passive"))
      (node (ref "C75") (pin "1") (pinfunction "1_1") (pintype "passive"))
      (node (ref "C76") (pin "1") (pinfunction "1_1") (pintype "passive"))
      (node (ref "C77") (pin "1") (pinfunction "1_1") (pintype "passive"))
      (node (ref "C78") (pin "1") (pinfunction "1_1") (pintype "passive"))
      (node (ref "C85") (pin "1") (pinfunction "1_1") (pintype "passive"))
      (node (ref "C86") (pin "1") (pinfunction "1_1") (pintype "passive"))
      (node (ref "C88") (pin "1") (pinfunction "1_1") (pintype "passive"))
      (node (ref "C89") (pin "1") (pinfunction "1_1") (pintype "passive"))
      (node (ref "C90") (pin "1") (pinfunction "1_1") (pintype "passive"))
      (node (ref "C91") (pin "2") (pinfunction "GND_1_2") (pintype "passive"))
      (node (ref "C91") (pin "4") (pinfunction "GND_2_4") (pintype "passive"))
      (node (ref "C92") (pin "2") (pinfunction "NEG_2") (pintype "passive"))
      (node (ref "J9") (pin "G1") (pinfunction "G1_G1") (pintype "power_in"))
      (node (ref "J9") (pin "G2") (pinfunction "G2_G2") (pintype "power_in"))
      (node (ref "T3") (pin "1") (pinfunction "UNBALANCED_PORT_(IN)_1") (pintype "input"))
      (node (ref "T5") (pin "2") (pinfunction "GND2_2") (pintype "bidirectional"))
      (node (ref "T5") (pin "5") (pinfunction "GND5_5") (pintype "bidirectional"))
      (node (ref "U4") (pin "1") (pinfunction "VC-TCXO/TCXO_1") (pintype "passive"))
      (node (ref "U4") (pin "2") (pinfunction "GND_2") (pintype "power_in"))
      (node (ref "U5") (pin "15") (pinfunction "VSN_1_15") (pintype "passive"))
      (node (ref "U5") (pin "18") (pinfunction "VSN_2_18") (pintype "passive"))
      (node (ref "U5") (pin "19") (pinfunction "VSN_3_19") (pintype "passive"))
      (node (ref "U5") (pin "22") (pinfunction "VSN_4_22") (pintype "passive"))
      (node (ref "U5") (pin "25") (pinfunction "VSN_5_25") (pintype "passive"))
      (node (ref "U5") (pin "49") (pinfunction "EP_49") (pintype "passive"))
      (node (ref "U5") (pin "5") (pinfunction "MIXS_IN/VSS_5") (pintype "passive"))
      (node (ref "X3") (pin "2") (pinfunction "GND_1_2") (pintype "passive"))
      (node (ref "X3") (pin "4") (pinfunction "GND_2_4") (pintype "passive"))
    )
    (net (code "48") (name "Net-(C4-Pad2)") (class "Default")
      (node (ref "C4") (pin "2") (pinfunction "2_2") (pintype "passive"))
      (node (ref "L15") (pin "1") (pinfunction "1_1") (pintype "passive"))
    )
    (net (code "49") (name "Net-(C5-Pad2)") (class "Default")
      (node (ref "C5") (pin "2") (pinfunction "2_2") (pintype "passive"))
      (node (ref "L10") (pin "2") (pinfunction "2_2") (pintype "passive"))
    )
    (net (code "50") (name "Net-(C12-Pad2)") (class "Default")
      (node (ref "C12") (pin "2") (pinfunction "2_2") (pintype "passive"))
      (node (ref "C14") (pin "1") (pinfunction "1_1") (pintype "passive"))
    )
    (net (code "51") (name "Net-(C32-Pad1)") (class "Default")
      (node (ref "C32") (pin "1") (pinfunction "1_1") (pintype "passive"))
      (node (ref "J9") (pin "A") (pinfunction "A_A") (pintype "passive"))
    )
    (net (code "52") (name "Net-(C91-INPUT)") (class "Default")
      (node (ref "C91") (pin "1") (pinfunction "INPUT_1") (pintype "passive"))
      (node (ref "FB1") (pin "2") (pinfunction "2_2") (pintype "passive"))
      (node (ref "FB5") (pin "2") (pinfunction "2_2") (pintype "passive"))
    )
    (net (code "53") (name "Net-(T3-BALANCED_PORT_(OUT_1))") (class "Default")
      (node (ref "C6") (pin "2") (pinfunction "2_2") (pintype "passive"))
      (node (ref "L15") (pin "2") (pinfunction "2_2") (pintype "passive"))
      (node (ref "T3") (pin "4") (pinfunction "BALANCED_PORT_(OUT_1)_4") (pintype "passive"))
    )
    (net (code "54") (name "Net-(T3-BALANCED_PORT_(OUT_2))") (class "Default")
      (node (ref "C7") (pin "1") (pinfunction "1_1") (pintype "passive"))
      (node (ref "L10") (pin "1") (pinfunction "1_1") (pintype "passive"))
      (node (ref "T3") (pin "3") (pinfunction "BALANCED_PORT_(OUT_2)_3") (pintype "passive"))
    )
    (net (code "55") (name "Net-(T3-GND)") (class "Default")
      (node (ref "T3") (pin "2") (pinfunction "GND_OR_DC_FEED+RF_GND_2") (pintype "passive"))
      (node (ref "T3") (pin "5") (pinfunction "GND_5") (pintype "passive"))
    )
    (net (code "56") (name "Net-(U4-OUTPUT)") (class "Default")
      (node (ref "C51") (pin "2") (pinfunction "2_2") (pintype "passive"))
      (node (ref "U4") (pin "3") (pinfunction "OUTPUT_3") (pintype "output"))
    )
    (net (code "57") (name "Net-(U4-VDD)") (class "Default")
      (node (ref "FB4") (pin "2") (pinfunction "2_2") (pintype "passive"))
      (node (ref "U4") (pin "4") (pinfunction "VDD_4") (pintype "power_in"))
    )
    (net (code "58") (name "Net-(U5-VEXT)") (class "Default")
      (node (ref "C13") (pin "2") (pinfunction "2_2") (pintype "passive"))
      (node (ref "FB5") (pin "1") (pinfunction "1_1") (pintype "passive"))
      (node (ref "U5") (pin "11") (pinfunction "VEXT_11") (pintype "passive"))
    )
    (net (code "59") (name "Net-(X3-CRYSTAL_1)") (class "Default")
      (node (ref "C111") (pin "1") (pinfunction "1_1") (pintype "passive"))
      (node (ref "R54") (pin "2") (pinfunction "2_2") (pintype "passive"))
      (node (ref "X3") (pin "1") (pinfunction "CRYSTAL_1_1") (pintype "passive"))
    )
    (net (code "60") (name "Net-(X3-CRYSTAL_2)") (class "Default")
      (node (ref "C110") (pin "1") (pinfunction "1_1") (pintype "passive"))
      (node (ref "R55") (pin "2") (pinfunction "2_2") (pintype "passive"))
      (node (ref "X3") (pin "3") (pinfunction "CRYSTAL_2_3") (pintype "passive"))
    )
    (net (code "61") (name "VBPD") (class "Default")
      (node (ref "C34") (pin "2") (pinfunction "2_2") (pintype "passive"))
      (node (ref "C52") (pin "2") (pinfunction "2_2") (pintype "passive"))
      (node (ref "U5") (pin "28") (pinfunction "V_DD_D_28") (pintype "passive"))
    )
    (net (code "62") (name "VDD_B") (class "Default")
      (node (ref "C57") (pin "1") (pinfunction "1_1") (pintype "passive"))
      (node (ref "C58") (pin "2") (pinfunction "2_2") (pintype "passive"))
      (node (ref "C77") (pin "2") (pinfunction "2_2") (pintype "passive"))
      (node (ref "C78") (pin "2") (pinfunction "2_2") (pintype "passive"))
      (node (ref "L3") (pin "1") (pinfunction "1_1") (pintype "passive"))
      (node (ref "L4") (pin "2") (pinfunction "2_2") (pintype "passive"))
      (node (ref "U5") (pin "12") (pinfunction "V_DD_B_12") (pintype "passive"))
    )
    (net (code "63") (name "VDD_PA") (class "Default")
      (node (ref "C66") (pin "2") (pinfunction "2_2") (pintype "passive"))
      (node (ref "C67") (pin "2") (pinfunction "2_2") (pintype "passive"))
      (node (ref "L1") (pin "2") (pinfunction "2_2") (pintype "passive"))
      (node (ref "L2") (pin "1") (pinfunction "1_1") (pintype "passive"))
      (node (ref "U5") (pin "13") (pinfunction "V_DD_PA_13") (pintype "passive"))
    )
    (net (code "64") (name "VSUP") (class "Default")
      (node (ref "C91") (pin "3") (pinfunction "OUTPUT_3") (pintype "passive"))
      (node (ref "C92") (pin "1") (pinfunction "POS_1") (pintype "passive"))
    )
    (net (code "65") (name "unconnected-(T3-NC-Pad6)") (class "Default")
      (node (ref "T3") (pin "6") (pinfunction "NC_6") (pintype "passive+no_connect"))
    )
    (net (code "66") (name "unconnected-(T5-NC-Pad6)") (class "Default")
      (node (ref "T5") (pin "6") (pinfunction "NC_6") (pintype "bidirectional+no_connect"))
    )
    (net (code "67") (name "unconnected-(U5-CLSYS-Pad36)") (class "Default")
      (node (ref "U5") (pin "36") (pinfunction "CLSYS_36") (pintype "passive+no_connect"))
    )
  )
)
